# Parachute_V1_5_openloadsensor.net
KiCad netlist of a schematic drawn in EAGLE
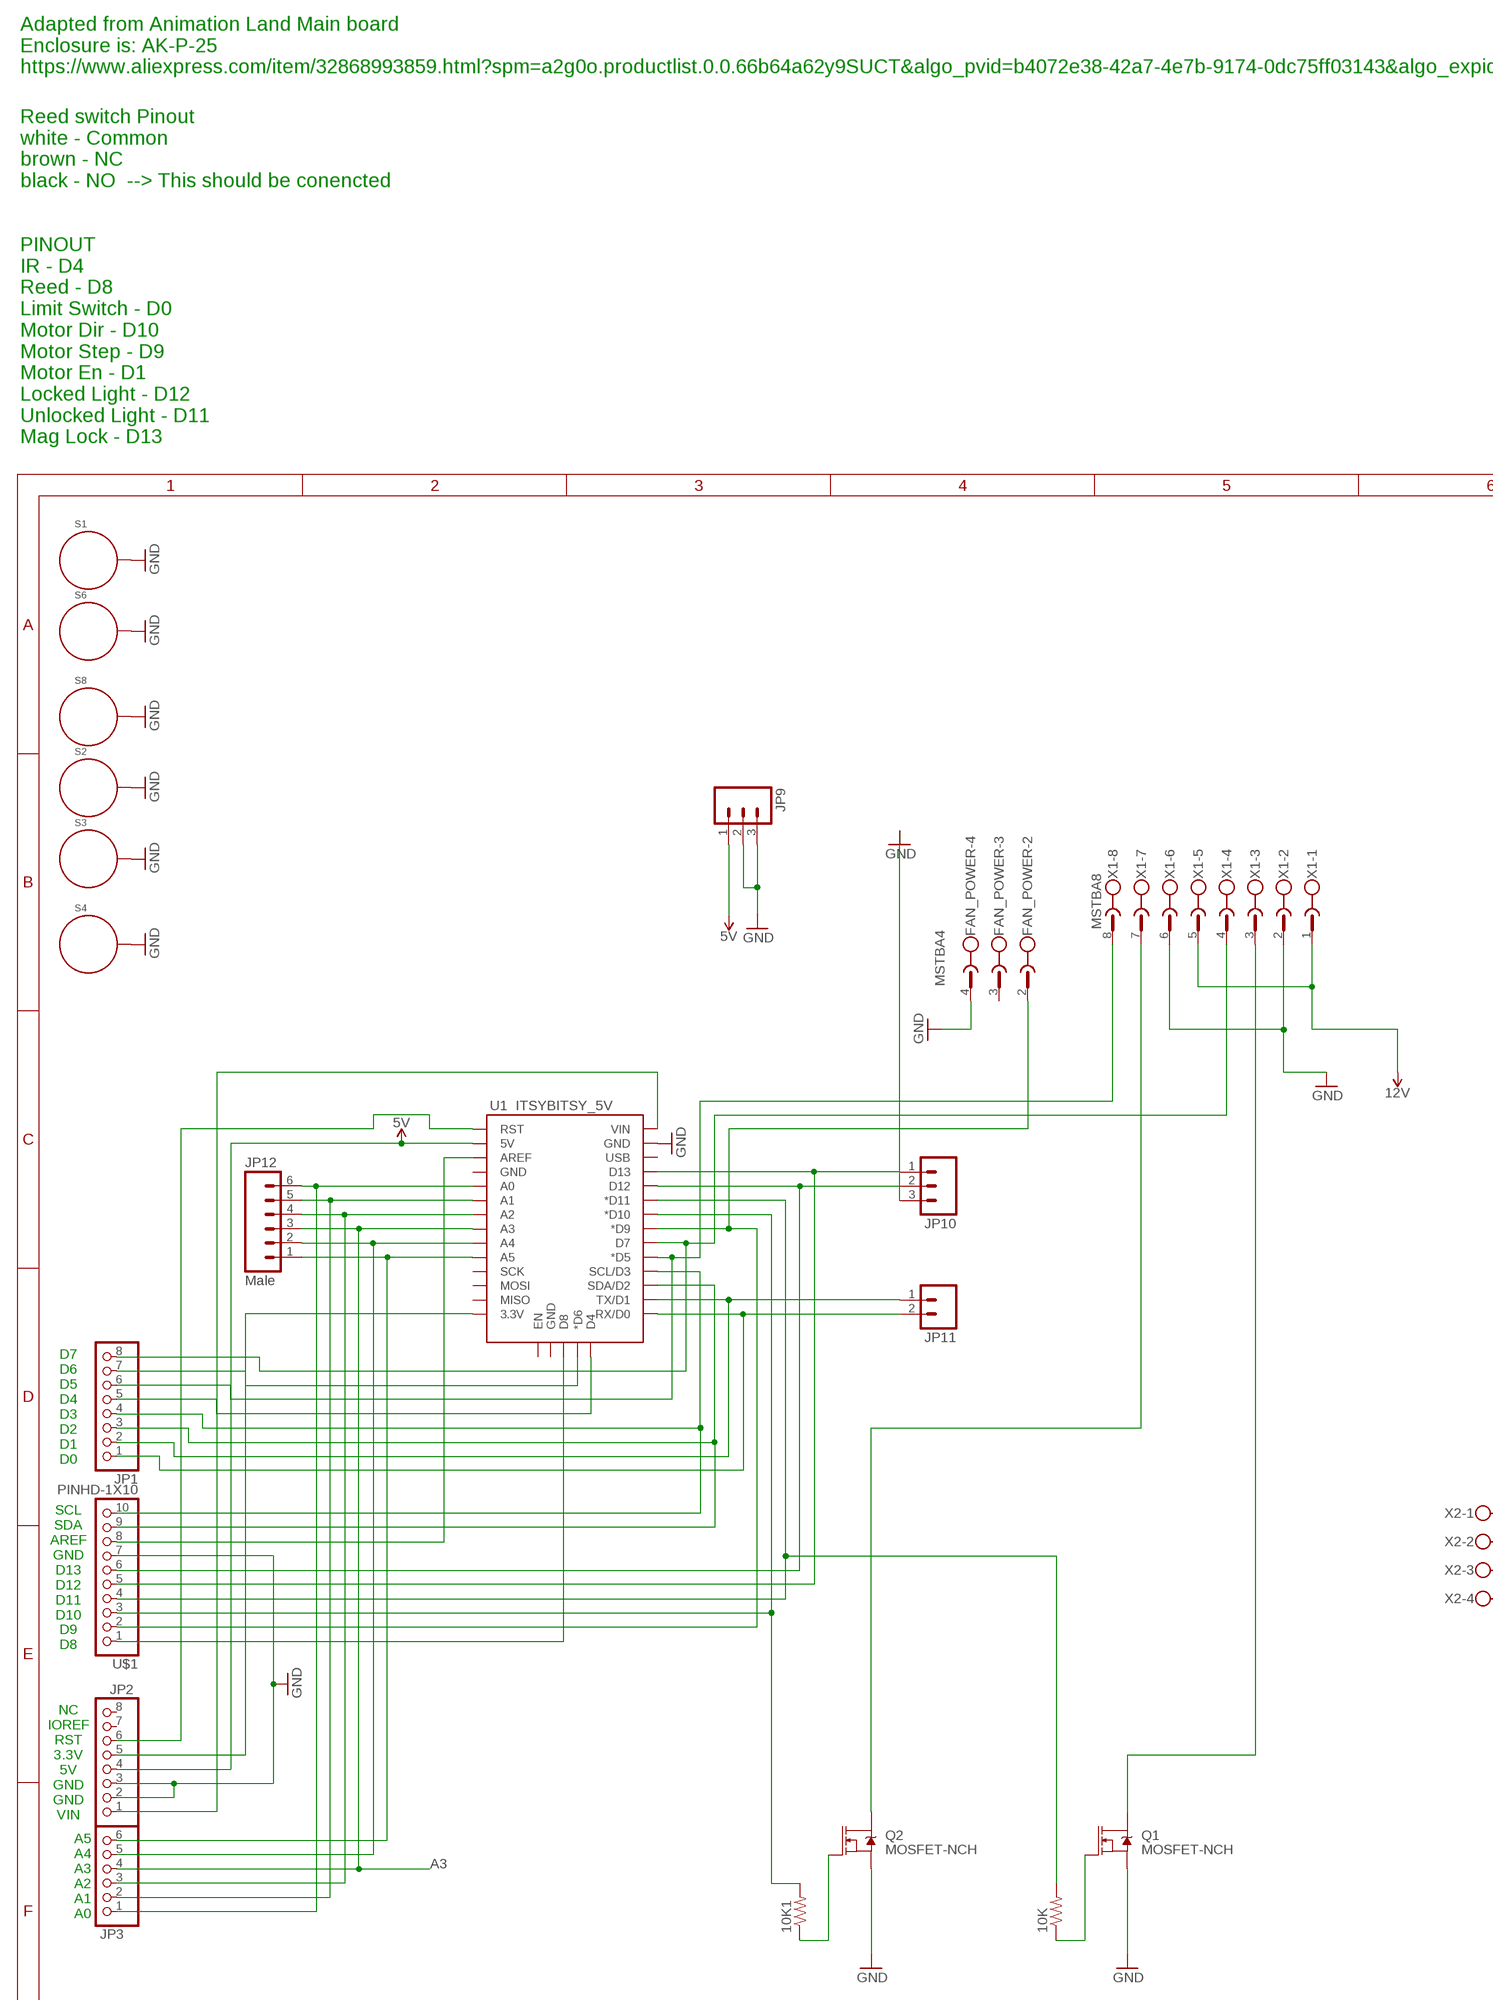
[diagram p0: schematic, sheet 1, part 1 of 2]
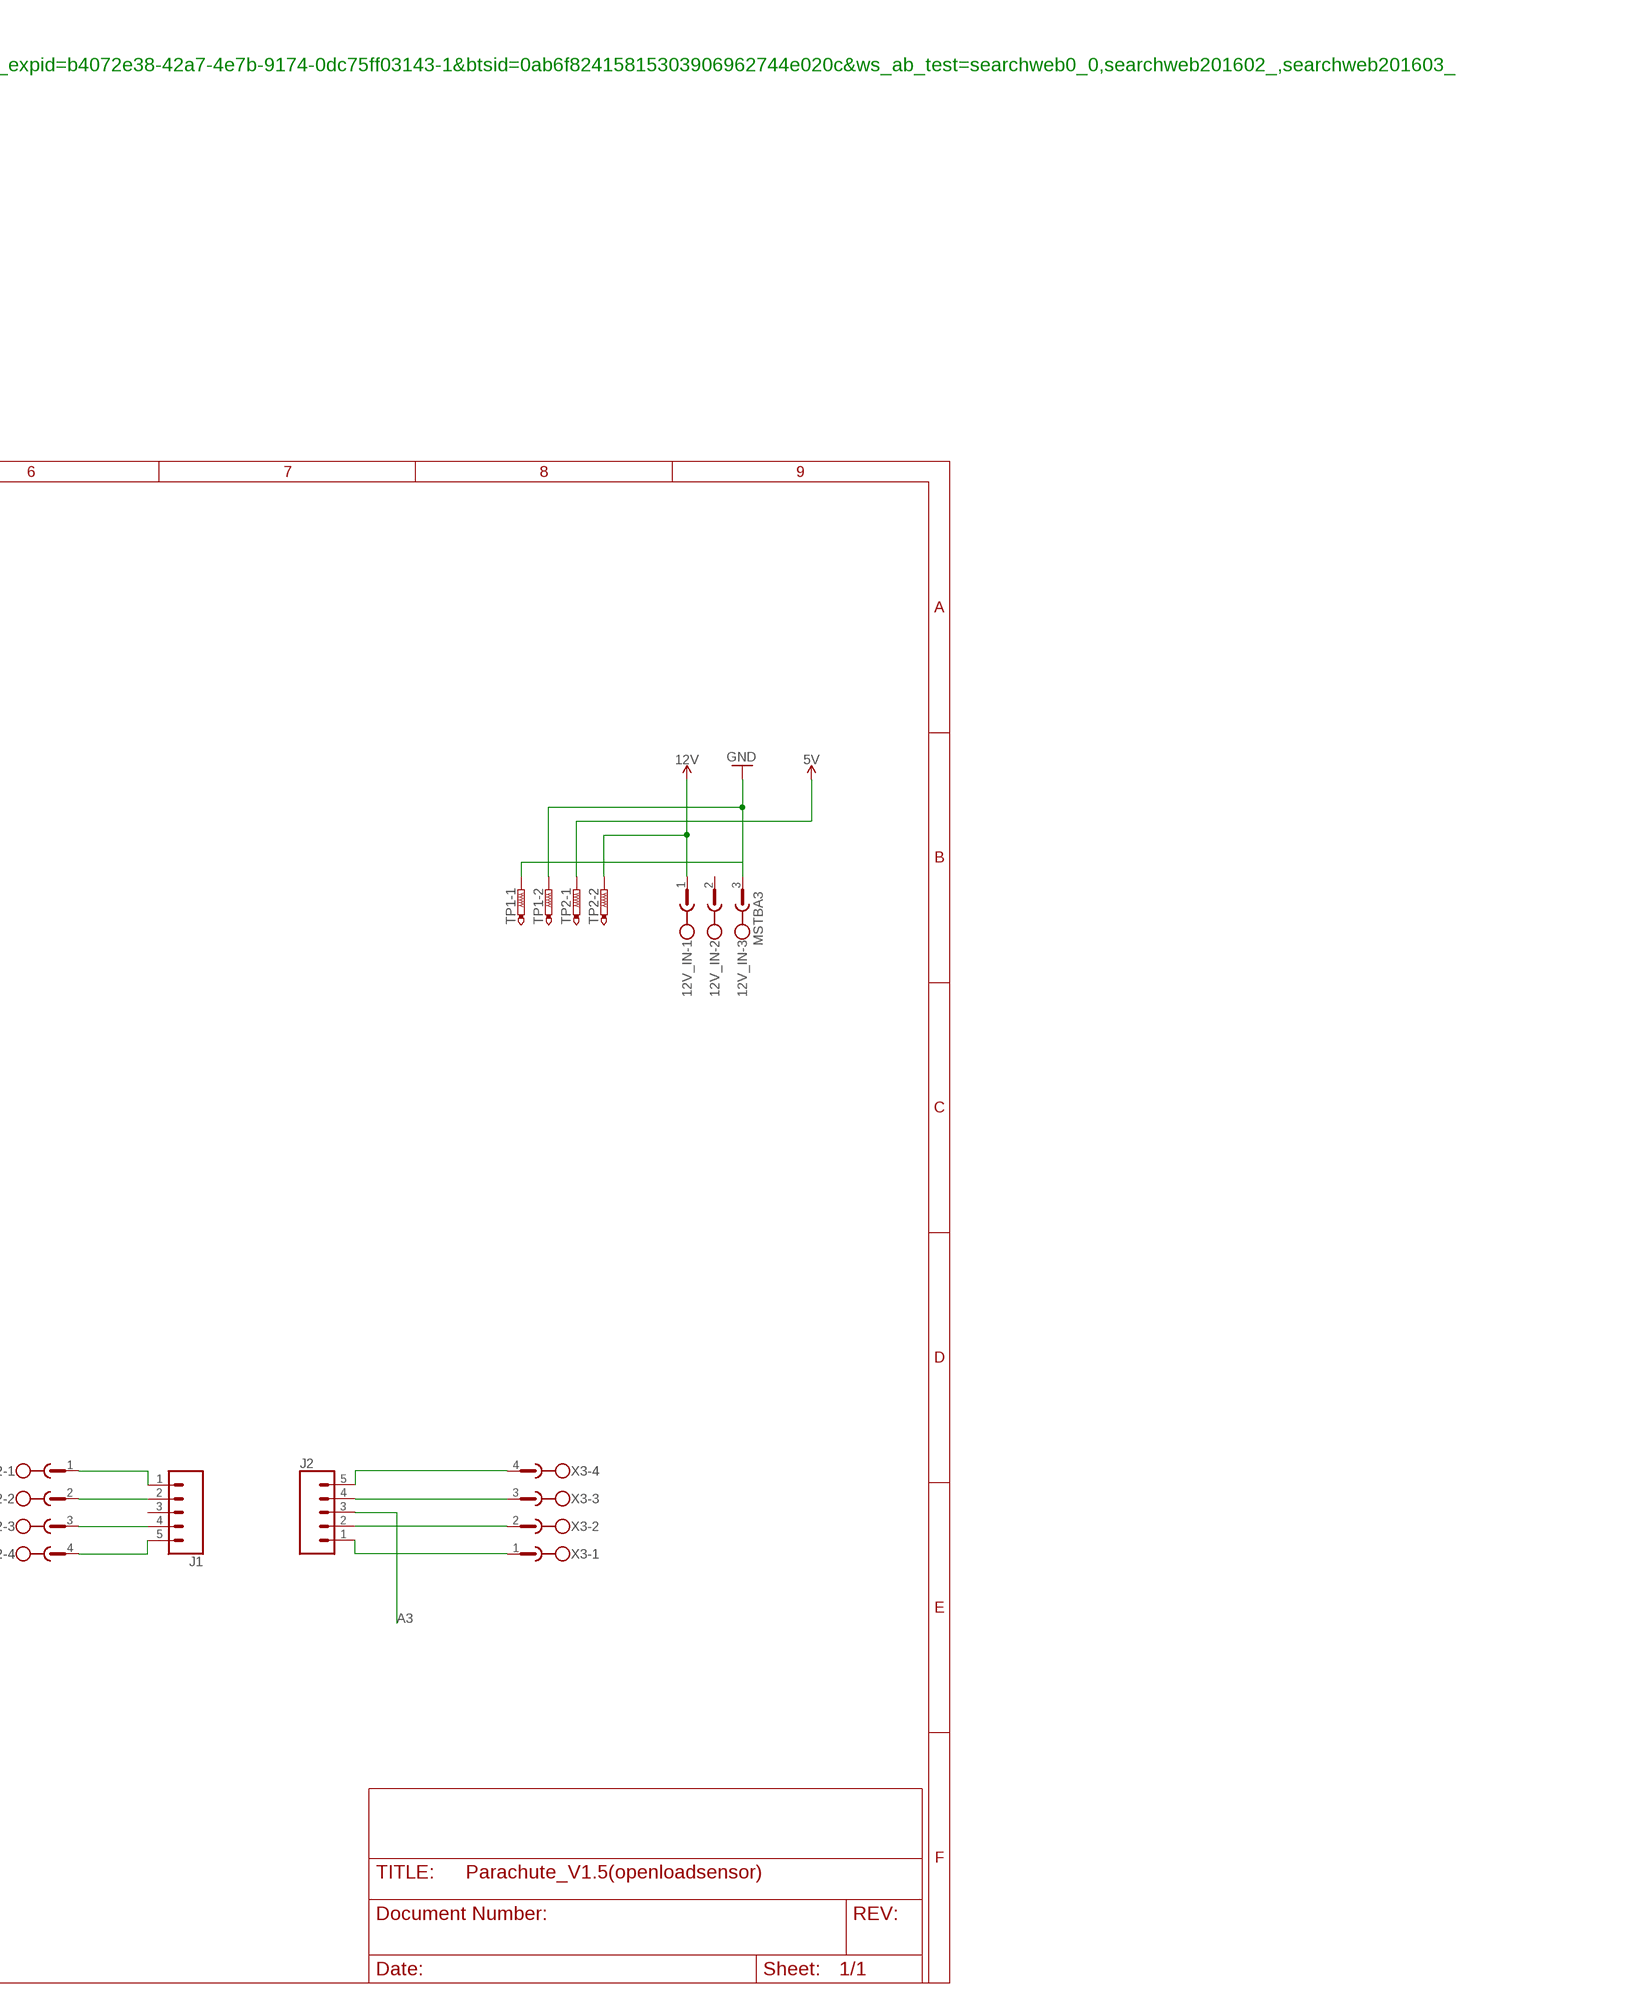
[diagram p1: schematic, sheet 1, part 2 of 2]

(export (version "E")
  (design (tool "Eeschema 10.0.6"))
  (components
    (comp (ref "10K")
      (value "R-US_M0805")
      (footprint "eagle-import:M0805")
      (libsource (lib "eagle-import") (part "R-US_M0805"))
    )
    (comp (ref "10K1")
      (value "R-US_M0805")
      (footprint "eagle-import:M0805")
      (libsource (lib "eagle-import") (part "R-US_M0805"))
    )
    (comp (ref "12V_IN")
      (value "MSTBA3")
      (footprint "eagle-import:MSTBA3")
      (fields (field (name "MF") "FARNELL") (field (name "MPN") "1757255"))
      (libsource (lib "eagle-import") (part "MSTBA3"))
    )
    (comp (ref "FAN_POWER")
      (value "MSTBA4")
      (footprint "eagle-import:MSTBA4")
      (fields (field (name "MF") "FARNELL") (field (name "MPN") "1757268"))
      (libsource (lib "eagle-import") (part "MSTBA4"))
    )
    (comp (ref "J1")
      (value "JST_CONN_05")
      (footprint "eagle-import:HEADER_PIN_1X05")
      (libsource (lib "eagle-import") (part "JST_CONN_05"))
    )
    (comp (ref "J2")
      (value "JST_CONN_05")
      (footprint "eagle-import:HEADER_PIN_1X05")
      (libsource (lib "eagle-import") (part "JST_CONN_05"))
    )
    (comp (ref "JP1")
      (value "PINHD-1X8CLEANBIG")
      (footprint "eagle-import:1X08-CLEANBIG")
      (libsource (lib "eagle-import") (part "PINHD-1X8CLEANBIG"))
    )
    (comp (ref "JP2")
      (value "PINHD-1X8CLEANBIG")
      (footprint "eagle-import:1X08-CLEANBIG")
      (libsource (lib "eagle-import") (part "PINHD-1X8CLEANBIG"))
    )
    (comp (ref "JP3")
      (value "PINHD-1X6B")
      (footprint "eagle-import:1X06-BIG")
      (libsource (lib "eagle-import") (part "PINHD-1X6B"))
    )
    (comp (ref "JP9")
      (value "M031X03_NO_SILK")
      (footprint "eagle-import:1X03_NO_SILK")
      (libsource (lib "eagle-import") (part "M031X03_NO_SILK"))
    )
    (comp (ref "JP10")
      (value "M031X03_NO_SILK")
      (footprint "eagle-import:1X03_NO_SILK")
      (libsource (lib "eagle-import") (part "M031X03_NO_SILK"))
    )
    (comp (ref "JP11")
      (value "M021X02_NO_SILK")
      (footprint "eagle-import:1X02_NO_SILK")
      (libsource (lib "eagle-import") (part "M021X02_NO_SILK"))
    )
    (comp (ref "JP12")
      (value "Male")
      (footprint "eagle-import:1X06")
      (libsource (lib "eagle-import") (part "M06SIP"))
    )
    (comp (ref "Q1")
      (value "MOSFET-NCH")
      (footprint "eagle-import:SO-8_POWER_PAK")
      (libsource (lib "eagle-import") (part "MOSFET-NCH"))
    )
    (comp (ref "Q2")
      (value "MOSFET-NCH")
      (footprint "eagle-import:SO-8_POWER_PAK")
      (libsource (lib "eagle-import") (part "MOSFET-NCH"))
    )
    (comp (ref "S1")
      (value "STANDOFF_ELECTRICAL5-32")
      (footprint "eagle-import:STANDOFF_ELECTRICAL_5_32")
      (libsource (lib "eagle-import") (part "STANDOFF_ELECTRICAL5-32"))
    )
    (comp (ref "S2")
      (value "STANDOFF_ELECTRICAL5-32")
      (footprint "eagle-import:STANDOFF_ELECTRICAL_5_32")
      (libsource (lib "eagle-import") (part "STANDOFF_ELECTRICAL5-32"))
    )
    (comp (ref "S3")
      (value "STANDOFF_ELECTRICAL5-32")
      (footprint "eagle-import:STANDOFF_ELECTRICAL_5_32")
      (libsource (lib "eagle-import") (part "STANDOFF_ELECTRICAL5-32"))
    )
    (comp (ref "S4")
      (value "STANDOFF_ELECTRICAL5-32")
      (footprint "eagle-import:STANDOFF_ELECTRICAL_5_32")
      (libsource (lib "eagle-import") (part "STANDOFF_ELECTRICAL5-32"))
    )
    (comp (ref "S6")
      (value "STANDOFF_ELECTRICAL5-32")
      (footprint "eagle-import:STANDOFF_ELECTRICAL_5_32")
      (libsource (lib "eagle-import") (part "STANDOFF_ELECTRICAL5-32"))
    )
    (comp (ref "S8")
      (value "STANDOFF_ELECTRICAL5-32")
      (footprint "eagle-import:STANDOFF_ELECTRICAL_5_32")
      (libsource (lib "eagle-import") (part "STANDOFF_ELECTRICAL5-32"))
    )
    (comp (ref "TP1")
      (value "PTR2")
      (footprint "eagle-import:P2-38-17")
      (libsource (lib "eagle-import") (part "PTR2"))
    )
    (comp (ref "TP2")
      (value "PTR2")
      (footprint "eagle-import:P2-38-17")
      (libsource (lib "eagle-import") (part "PTR2"))
    )
    (comp (ref "U$1")
      (value "PINHD-1X10")
      (footprint "eagle-import:1X10-BIG")
      (libsource (lib "eagle-import") (part "PINHD-1X10"))
    )
    (comp (ref "U1")
      (value "ITSYBITSY_5V")
      (footprint "eagle-import:ADAFRUIT_LENOARDO")
      (libsource (lib "eagle-import") (part "ITSYBITSY_5V"))
    )
    (comp (ref "X1")
      (value "MSTBA8")
      (footprint "eagle-import:MSTBA8")
      (fields (field (name "MF") "FARNELL") (field (name "MPN") "1757307"))
      (libsource (lib "eagle-import") (part "MSTBA8"))
    )
    (comp (ref "X2")
      (value "PHOENIX_508_4PIN")
      (footprint "eagle-import:PHOENIX_508_4PIN")
      (fields (field (name "MF") "FARNELL") (field (name "MPN") "1757268"))
      (libsource (lib "eagle-import") (part "PHOENIX_508_4PIN"))
    )
    (comp (ref "X3")
      (value "PHOENIX_508_4PIN")
      (footprint "eagle-import:PHOENIX_508_4PIN")
      (fields (field (name "MF") "FARNELL") (field (name "MPN") "1757268"))
      (libsource (lib "eagle-import") (part "PHOENIX_508_4PIN"))
    )
  )
  (nets
    (net (code "1") (name "/A3") (class "Default")
      (node (ref "J2") (pin "3") (pinfunction "3_3") (pintype "passive"))
      (node (ref "JP12") (pin "3") (pinfunction "3_3") (pintype "passive"))
      (node (ref "JP3") (pin "4") (pinfunction "4_4") (pintype "passive"))
      (node (ref "U1") (pin "A3") (pinfunction "A3_A3") (pintype "bidirectional"))
    )
    (net (code "2") (name "5V") (class "Default")
      (node (ref "JP2") (pin "4") (pinfunction "4_4") (pintype "passive"))
      (node (ref "JP9") (pin "1") (pinfunction "1_1") (pintype "passive"))
      (node (ref "TP2") (pin "TP-1") (pinfunction "TP_TP-1") (pintype "input"))
      (node (ref "U1") (pin "5V") (pinfunction "5V_5V") (pintype "bidirectional"))
    )
    (net (code "3") (name "12V") (class "Default")
      (node (ref "12V_IN") (pin "1") (pinfunction "1_1") (pintype "passive"))
      (node (ref "TP2") (pin "TP-2") (pinfunction "TP_TP-2") (pintype "input"))
      (node (ref "X1") (pin "1") (pinfunction "1_1") (pintype "passive"))
      (node (ref "X1") (pin "5") (pinfunction "1_5") (pintype "passive"))
    )
    (net (code "4") (name "GND") (class "Default")
      (node (ref "12V_IN") (pin "3") (pinfunction "1_3") (pintype "passive"))
      (node (ref "FAN_POWER") (pin "4") (pinfunction "1_4") (pintype "passive"))
      (node (ref "JP10") (pin "3") (pinfunction "3_3") (pintype "passive"))
      (node (ref "JP2") (pin "2") (pinfunction "2_2") (pintype "passive"))
      (node (ref "JP2") (pin "3") (pinfunction "3_3") (pintype "passive"))
      (node (ref "JP9") (pin "2") (pinfunction "2_2") (pintype "passive"))
      (node (ref "JP9") (pin "3") (pinfunction "3_3") (pintype "passive"))
      (node (ref "Q1") (pin "S") (pinfunction "S_S") (pintype "bidirectional"))
      (node (ref "Q2") (pin "S") (pinfunction "S_S") (pintype "bidirectional"))
      (node (ref "S1") (pin "P1") (pinfunction "P$1_P1") (pintype "bidirectional"))
      (node (ref "S2") (pin "P1") (pinfunction "P$1_P1") (pintype "bidirectional"))
      (node (ref "S3") (pin "P1") (pinfunction "P$1_P1") (pintype "bidirectional"))
      (node (ref "S4") (pin "P1") (pinfunction "P$1_P1") (pintype "bidirectional"))
      (node (ref "S6") (pin "P1") (pinfunction "P$1_P1") (pintype "bidirectional"))
      (node (ref "S8") (pin "P1") (pinfunction "P$1_P1") (pintype "bidirectional"))
      (node (ref "TP1") (pin "TP-1") (pinfunction "TP_TP-1") (pintype "input"))
      (node (ref "TP1") (pin "TP-2") (pinfunction "TP_TP-2") (pintype "input"))
      (node (ref "U$1") (pin "7") (pinfunction "7_7") (pintype "passive"))
      (node (ref "U1") (pin "GND@2") (pinfunction "GND_GND@2") (pintype "bidirectional"))
      (node (ref "X1") (pin "2") (pinfunction "1_2") (pintype "passive"))
      (node (ref "X1") (pin "6") (pinfunction "1_6") (pintype "passive"))
    )
    (net (code "5") (name "Net-(10K-Pad1)") (class "Default")
      (node (ref "10K") (pin "1") (pinfunction "1_1") (pintype "passive"))
      (node (ref "Q1") (pin "G") (pinfunction "G_G") (pintype "bidirectional"))
    )
    (net (code "6") (name "Net-(10K1-Pad1)") (class "Default")
      (node (ref "10K1") (pin "1") (pinfunction "1_1") (pintype "passive"))
      (node (ref "Q2") (pin "G") (pinfunction "G_G") (pintype "bidirectional"))
    )
    (net (code "7") (name "Net-(FAN_POWERB-1)") (class "Default")
      (node (ref "FAN_POWER") (pin "2") (pinfunction "1_2") (pintype "passive"))
      (node (ref "U$1") (pin "2") (pinfunction "2_2") (pintype "passive"))
      (node (ref "U1") (pin "D9") (pinfunction "*D9_D9") (pintype "bidirectional"))
    )
    (net (code "8") (name "Net-(J1-Pad1)") (class "Default")
      (node (ref "J1") (pin "1") (pinfunction "1_1") (pintype "passive"))
      (node (ref "X2") (pin "1") (pinfunction "1_1") (pintype "passive"))
    )
    (net (code "9") (name "Net-(J2-Pad1)") (class "Default")
      (node (ref "J2") (pin "1") (pinfunction "1_1") (pintype "passive"))
      (node (ref "X3") (pin "1") (pinfunction "1_1") (pintype "passive"))
    )
    (net (code "10") (name "Net-(JP1-Pad5)") (class "Default")
      (node (ref "JP1") (pin "5") (pinfunction "5_5") (pintype "passive"))
      (node (ref "U1") (pin "D4") (pinfunction "D4_D4") (pintype "bidirectional"))
    )
    (net (code "11") (name "Net-(JP2-Pad1)") (class "Default")
      (node (ref "JP2") (pin "1") (pinfunction "1_1") (pintype "passive"))
      (node (ref "U1") (pin "VIN") (pinfunction "VIN_VIN") (pintype "bidirectional"))
    )
    (net (code "12") (name "Net-(JP10-Pad1)") (class "Default")
      (node (ref "JP10") (pin "1") (pinfunction "1_1") (pintype "passive"))
      (node (ref "U$1") (pin "5") (pinfunction "5_5") (pintype "passive"))
      (node (ref "U1") (pin "D13") (pinfunction "D13_D13") (pintype "bidirectional"))
    )
    (net (code "13") (name "Net-(JP10-Pad2)") (class "Default")
      (node (ref "JP10") (pin "2") (pinfunction "2_2") (pintype "passive"))
      (node (ref "U$1") (pin "6") (pinfunction "6_6") (pintype "passive"))
      (node (ref "U1") (pin "D12") (pinfunction "D12_D12") (pintype "bidirectional"))
    )
    (net (code "14") (name "Net-(JP12-Pad1)") (class "Default")
      (node (ref "JP12") (pin "1") (pinfunction "1_1") (pintype "passive"))
      (node (ref "JP3") (pin "6") (pinfunction "6_6") (pintype "passive"))
      (node (ref "U1") (pin "A5") (pinfunction "A5_A5") (pintype "bidirectional"))
    )
    (net (code "15") (name "Net-(JP12-Pad2)") (class "Default")
      (node (ref "JP12") (pin "2") (pinfunction "2_2") (pintype "passive"))
      (node (ref "JP3") (pin "5") (pinfunction "5_5") (pintype "passive"))
      (node (ref "U1") (pin "A4") (pinfunction "A4_A4") (pintype "bidirectional"))
    )
    (net (code "16") (name "Net-(JP12-Pad4)") (class "Default")
      (node (ref "JP12") (pin "4") (pinfunction "4_4") (pintype "passive"))
      (node (ref "JP3") (pin "3") (pinfunction "3_3") (pintype "passive"))
      (node (ref "U1") (pin "A2") (pinfunction "A2_A2") (pintype "bidirectional"))
    )
    (net (code "17") (name "Net-(JP12-Pad5)") (class "Default")
      (node (ref "JP12") (pin "5") (pinfunction "5_5") (pintype "passive"))
      (node (ref "JP3") (pin "2") (pinfunction "2_2") (pintype "passive"))
      (node (ref "U1") (pin "A1") (pinfunction "A1_A1") (pintype "bidirectional"))
    )
    (net (code "18") (name "Net-(JP12-Pad6)") (class "Default")
      (node (ref "JP12") (pin "6") (pinfunction "6_6") (pintype "passive"))
      (node (ref "JP3") (pin "1") (pinfunction "1_1") (pintype "passive"))
      (node (ref "U1") (pin "A0") (pinfunction "A0_A0") (pintype "bidirectional"))
    )
    (net (code "19") (name "Net-(Q1-D)") (class "Default")
      (node (ref "Q1") (pin "D1") (pinfunction "D_D1") (pintype "bidirectional"))
      (node (ref "X1") (pin "3") (pinfunction "1_3") (pintype "passive"))
    )
    (net (code "20") (name "Net-(Q2-D)") (class "Default")
      (node (ref "Q2") (pin "D1") (pinfunction "D_D1") (pintype "bidirectional"))
      (node (ref "X1") (pin "7") (pinfunction "1_7") (pintype "passive"))
    )
    (net (code "21") (name "Net-(U$1-Pad1)") (class "Default")
      (node (ref "U$1") (pin "1") (pinfunction "1_1") (pintype "passive"))
      (node (ref "U1") (pin "D8") (pinfunction "D8_D8") (pintype "bidirectional"))
    )
    (net (code "22") (name "Net-(U$1-Pad8)") (class "Default")
      (node (ref "U$1") (pin "8") (pinfunction "8_8") (pintype "passive"))
      (node (ref "U1") (pin "AREF") (pinfunction "AREF_AREF") (pintype "bidirectional"))
    )
    (net (code "23") (name "Net-(U1-*D5)") (class "Default")
      (node (ref "JP1") (pin "6") (pinfunction "6_6") (pintype "passive"))
      (node (ref "U1") (pin "D5") (pinfunction "*D5_D5") (pintype "bidirectional"))
      (node (ref "X1") (pin "8") (pinfunction "1_8") (pintype "passive"))
    )
    (net (code "24") (name "Net-(U1-*D6)") (class "Default")
      (node (ref "JP1") (pin "7") (pinfunction "7_7") (pintype "passive"))
      (node (ref "U1") (pin "D6") (pinfunction "*D6_D6") (pintype "bidirectional"))
    )
    (net (code "25") (name "Net-(U1-*D10)") (class "Default")
      (node (ref "10K1") (pin "2") (pinfunction "2_2") (pintype "passive"))
      (node (ref "U$1") (pin "3") (pinfunction "3_3") (pintype "passive"))
      (node (ref "U1") (pin "D10") (pinfunction "*D10_D10") (pintype "bidirectional"))
    )
    (net (code "26") (name "Net-(U1-*D11)") (class "Default")
      (node (ref "10K") (pin "2") (pinfunction "2_2") (pintype "passive"))
      (node (ref "U$1") (pin "4") (pinfunction "4_4") (pintype "passive"))
      (node (ref "U1") (pin "D11") (pinfunction "*D11_D11") (pintype "bidirectional"))
    )
    (net (code "27") (name "Net-(U1-3.3V)") (class "Default")
      (node (ref "JP2") (pin "5") (pinfunction "5_5") (pintype "passive"))
      (node (ref "U1") (pin "3V") (pinfunction "3.3V_3V") (pintype "bidirectional"))
    )
    (net (code "28") (name "Net-(U1-RST)") (class "Default")
      (node (ref "JP2") (pin "6") (pinfunction "6_6") (pintype "passive"))
      (node (ref "U1") (pin "RES") (pinfunction "RST_RES") (pintype "bidirectional"))
    )
    (net (code "29") (name "Net-(U1-RX{slash}D0)") (class "Default")
      (node (ref "JP1") (pin "1") (pinfunction "1_1") (pintype "passive"))
      (node (ref "JP11") (pin "2") (pinfunction "2_2") (pintype "passive"))
      (node (ref "U1") (pin "RX") (pinfunction "RX/D0_RX") (pintype "bidirectional"))
    )
    (net (code "30") (name "Net-(U1-SCL{slash}D3)") (class "Default")
      (node (ref "JP1") (pin "4") (pinfunction "4_4") (pintype "passive"))
      (node (ref "U$1") (pin "10") (pinfunction "10_10") (pintype "passive"))
      (node (ref "U1") (pin "SCL") (pinfunction "SCL/D3_SCL") (pintype "bidirectional"))
    )
    (net (code "31") (name "Net-(U1-SDA{slash}D2)") (class "Default")
      (node (ref "JP1") (pin "3") (pinfunction "3_3") (pintype "passive"))
      (node (ref "U$1") (pin "9") (pinfunction "9_9") (pintype "passive"))
      (node (ref "U1") (pin "SDA") (pinfunction "SDA/D2_SDA") (pintype "bidirectional"))
    )
    (net (code "32") (name "Net-(U1-TX{slash}D1)") (class "Default")
      (node (ref "JP1") (pin "2") (pinfunction "2_2") (pintype "passive"))
      (node (ref "JP11") (pin "1") (pinfunction "1_1") (pintype "passive"))
      (node (ref "U1") (pin "TX") (pinfunction "TX/D1_TX") (pintype "bidirectional"))
    )
    (net (code "33") (name "Net-(X1D-1)") (class "Default")
      (node (ref "JP1") (pin "8") (pinfunction "8_8") (pintype "passive"))
      (node (ref "U1") (pin "D7") (pinfunction "D7_D7") (pintype "bidirectional"))
      (node (ref "X1") (pin "4") (pinfunction "1_4") (pintype "passive"))
    )
    (net (code "34") (name "Net-(X2B-1)") (class "Default")
      (node (ref "J1") (pin "2") (pinfunction "2_2") (pintype "passive"))
      (node (ref "X2") (pin "2") (pinfunction "1_2") (pintype "passive"))
    )
    (net (code "35") (name "Net-(X2C-1)") (class "Default")
      (node (ref "J1") (pin "4") (pinfunction "4_4") (pintype "passive"))
      (node (ref "X2") (pin "3") (pinfunction "1_3") (pintype "passive"))
    )
    (net (code "36") (name "Net-(X2D-1)") (class "Default")
      (node (ref "J1") (pin "5") (pinfunction "5_5") (pintype "passive"))
      (node (ref "X2") (pin "4") (pinfunction "1_4") (pintype "passive"))
    )
    (net (code "37") (name "Net-(X3B-1)") (class "Default")
      (node (ref "J2") (pin "2") (pinfunction "2_2") (pintype "passive"))
      (node (ref "X3") (pin "2") (pinfunction "1_2") (pintype "passive"))
    )
    (net (code "38") (name "Net-(X3C-1)") (class "Default")
      (node (ref "J2") (pin "4") (pinfunction "4_4") (pintype "passive"))
      (node (ref "X3") (pin "3") (pinfunction "1_3") (pintype "passive"))
    )
    (net (code "39") (name "Net-(X3D-1)") (class "Default")
      (node (ref "J2") (pin "5") (pinfunction "5_5") (pintype "passive"))
      (node (ref "X3") (pin "4") (pinfunction "1_4") (pintype "passive"))
    )
    (net (code "40") (name "unconnected-(12V_INB-1-Pad2)") (class "Default")
      (node (ref "12V_IN") (pin "2") (pinfunction "1_2") (pintype "passive"))
    )
    (net (code "41") (name "unconnected-(FAN_POWERC-1-Pad3)") (class "Default")
      (node (ref "FAN_POWER") (pin "3") (pinfunction "1_3") (pintype "passive"))
    )
    (net (code "42") (name "unconnected-(J1-Pad3)") (class "Default")
      (node (ref "J1") (pin "3") (pinfunction "3_3") (pintype "passive"))
    )
    (net (code "43") (name "unconnected-(JP2-Pad7)") (class "Default")
      (node (ref "JP2") (pin "7") (pinfunction "7_7") (pintype "passive"))
    )
    (net (code "44") (name "unconnected-(JP2-Pad8)") (class "Default")
      (node (ref "JP2") (pin "8") (pinfunction "8_8") (pintype "passive"))
    )
    (net (code "45") (name "unconnected-(U1-GND-PadGND@0)") (class "Default")
      (node (ref "U1") (pin "GND@0") (pinfunction "GND_GND@0") (pintype "bidirectional"))
    )
    (net (code "46") (name "unconnected-(U1-GND-PadGND@1)") (class "Default")
      (node (ref "U1") (pin "GND@1") (pinfunction "GND_GND@1") (pintype "bidirectional"))
    )
    (net (code "47") (name "unconnected-(U1-PadEN)") (class "Default")
      (node (ref "U1") (pin "EN") (pinfunction "EN_EN") (pintype "bidirectional"))
    )
    (net (code "48") (name "unconnected-(U1-PadMISO)") (class "Default")
      (node (ref "U1") (pin "MISO") (pinfunction "MISO_MISO") (pintype "bidirectional"))
    )
    (net (code "49") (name "unconnected-(U1-PadMOSI)") (class "Default")
      (node (ref "U1") (pin "MOSI") (pinfunction "MOSI_MOSI") (pintype "bidirectional"))
    )
    (net (code "50") (name "unconnected-(U1-PadSCK)") (class "Default")
      (node (ref "U1") (pin "SCK") (pinfunction "SCK_SCK") (pintype "bidirectional"))
    )
    (net (code "51") (name "unconnected-(U1-PadUSB)") (class "Default")
      (node (ref "U1") (pin "USB") (pinfunction "USB_USB") (pintype "bidirectional"))
    )
  )
)
